# Current_Sensor.net
KiCad netlist of a schematic drawn in Altium Designer
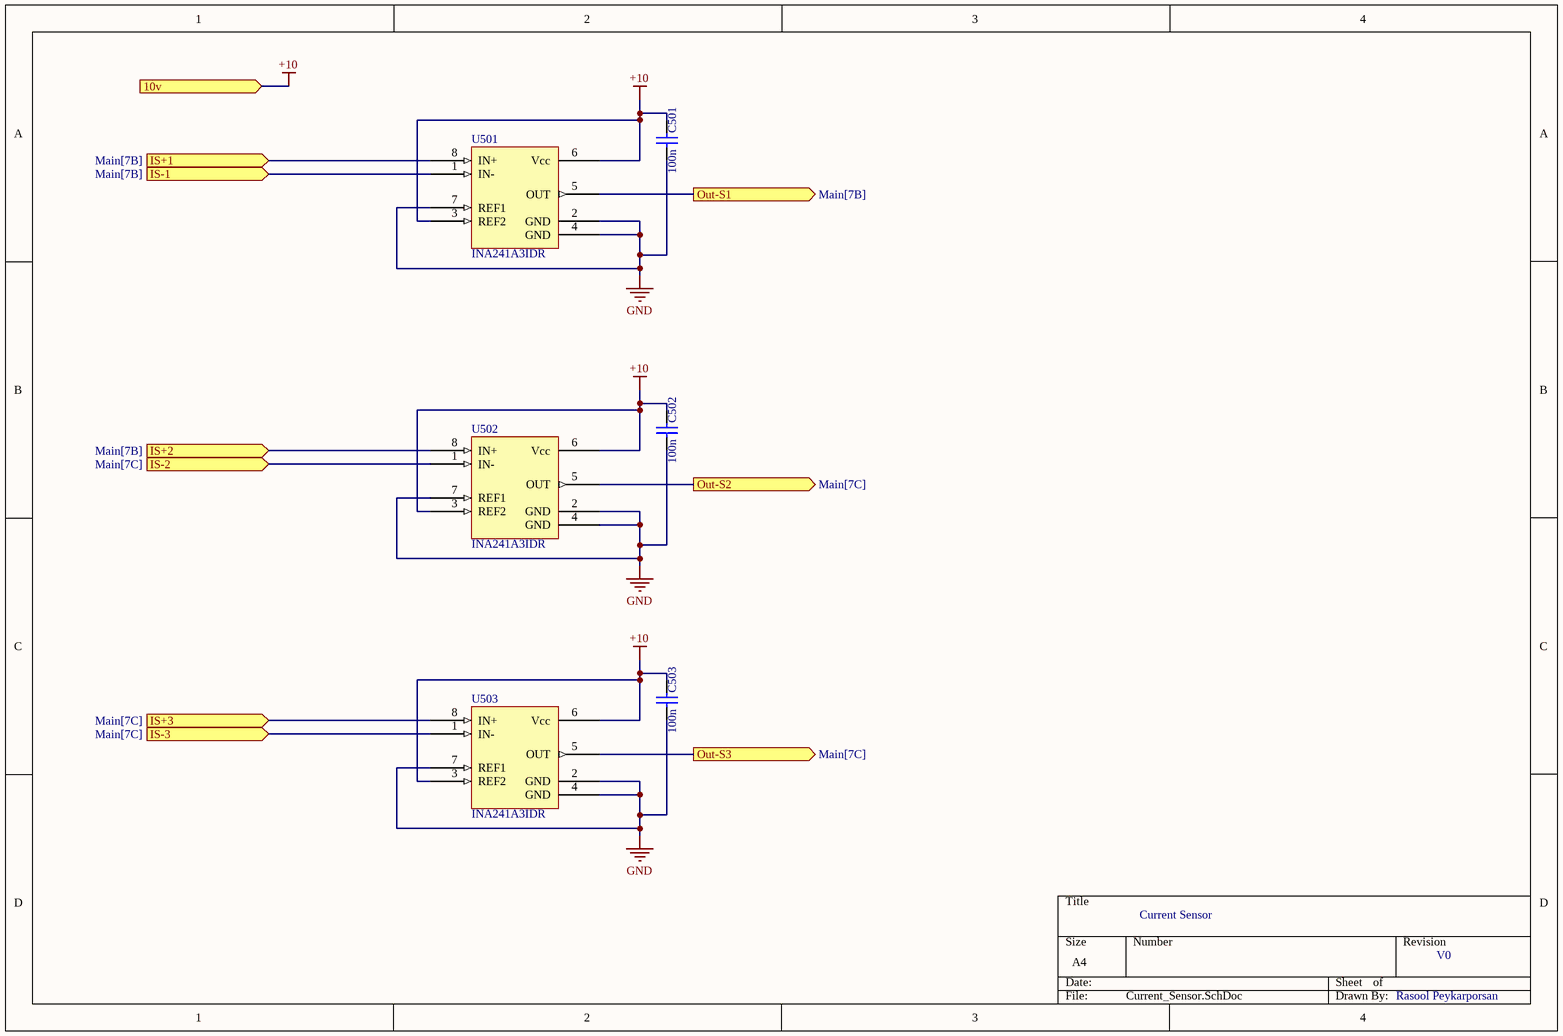
[diagram p0: Current_Sensor.SchDoc]

(export (version "E")
  (design (tool "Eeschema 10.0.6"))
  (components
    (comp (ref "C501")
      (value "100n")
      (footprint "CAP_1206")
      (description "Non Polarized Capacitor, SMD, 1206")
      (libsource (lib "Resistors and Capacitors") (part "CAPN 1206"))
    )
    (comp (ref "C502")
      (value "100n")
      (footprint "CAP_1206")
      (description "Non Polarized Capacitor, SMD, 1206")
      (libsource (lib "Resistors and Capacitors") (part "CAPN 1206"))
    )
    (comp (ref "C503")
      (value "100n")
      (footprint "CAP_1206")
      (description "Non Polarized Capacitor, SMD, 1206")
      (libsource (lib "Resistors and Capacitors") (part "CAPN 1206"))
    )
    (comp (ref "U501")
      (value "INA241A3IDR")
      (footprint "8SOIC-M")
      (description "Current Sense Amplifier 1 Circuit Single-Ended 8-SOIC")
      (libsource (lib "Schematics") (part "INA241A3IDR"))
    )
    (comp (ref "U502")
      (value "INA241A3IDR")
      (footprint "8SOIC-M")
      (description "Current Sense Amplifier 1 Circuit Single-Ended 8-SOIC")
      (libsource (lib "Schematics") (part "INA241A3IDR"))
    )
    (comp (ref "U503")
      (value "INA241A3IDR")
      (footprint "8SOIC-M")
      (description "Current Sense Amplifier 1 Circuit Single-Ended 8-SOIC")
      (libsource (lib "Schematics") (part "INA241A3IDR"))
    )
  )
  (nets
    (net (code "1") (name "+10") (class "Default")
      (node (ref "C501") (pin "2") (pinfunction "2_2") (pintype "passive"))
      (node (ref "C502") (pin "2") (pinfunction "2_2") (pintype "passive"))
      (node (ref "C503") (pin "2") (pinfunction "2_2") (pintype "passive"))
      (node (ref "U501") (pin "3") (pinfunction "REF2_3") (pintype "input"))
      (node (ref "U501") (pin "6") (pinfunction "Vcc_6") (pintype "power_in"))
      (node (ref "U502") (pin "3") (pinfunction "REF2_3") (pintype "input"))
      (node (ref "U502") (pin "6") (pinfunction "Vcc_6") (pintype "power_in"))
      (node (ref "U503") (pin "3") (pinfunction "REF2_3") (pintype "input"))
      (node (ref "U503") (pin "6") (pinfunction "Vcc_6") (pintype "power_in"))
    )
    (net (code "2") (name "/IS+1") (class "Default")
      (node (ref "U501") (pin "8") (pinfunction "IN+_8") (pintype "input"))
    )
    (net (code "3") (name "/IS+2") (class "Default")
      (node (ref "U502") (pin "8") (pinfunction "IN+_8") (pintype "input"))
    )
    (net (code "4") (name "/IS+3") (class "Default")
      (node (ref "U503") (pin "8") (pinfunction "IN+_8") (pintype "input"))
    )
    (net (code "5") (name "/IS-1") (class "Default")
      (node (ref "U501") (pin "1") (pinfunction "IN-_1") (pintype "input"))
    )
    (net (code "6") (name "/IS-2") (class "Default")
      (node (ref "U502") (pin "1") (pinfunction "IN-_1") (pintype "input"))
    )
    (net (code "7") (name "/IS-3") (class "Default")
      (node (ref "U503") (pin "1") (pinfunction "IN-_1") (pintype "input"))
    )
    (net (code "8") (name "/Out-S1") (class "Default")
      (node (ref "U501") (pin "5") (pinfunction "OUT_5") (pintype "output"))
    )
    (net (code "9") (name "/Out-S2") (class "Default")
      (node (ref "U502") (pin "5") (pinfunction "OUT_5") (pintype "output"))
    )
    (net (code "10") (name "/Out-S3") (class "Default")
      (node (ref "U503") (pin "5") (pinfunction "OUT_5") (pintype "output"))
    )
    (net (code "11") (name "GND") (class "Default")
      (node (ref "C501") (pin "1") (pinfunction "1_1") (pintype "passive"))
      (node (ref "C502") (pin "1") (pinfunction "1_1") (pintype "passive"))
      (node (ref "C503") (pin "1") (pinfunction "1_1") (pintype "passive"))
      (node (ref "U501") (pin "2") (pinfunction "GND_2") (pintype "power_in"))
      (node (ref "U501") (pin "4") (pinfunction "GND_4") (pintype "passive"))
      (node (ref "U501") (pin "7") (pinfunction "REF1_7") (pintype "input"))
      (node (ref "U502") (pin "2") (pinfunction "GND_2") (pintype "power_in"))
      (node (ref "U502") (pin "4") (pinfunction "GND_4") (pintype "passive"))
      (node (ref "U502") (pin "7") (pinfunction "REF1_7") (pintype "input"))
      (node (ref "U503") (pin "2") (pinfunction "GND_2") (pintype "power_in"))
      (node (ref "U503") (pin "4") (pinfunction "GND_4") (pintype "passive"))
      (node (ref "U503") (pin "7") (pinfunction "REF1_7") (pintype "input"))
    )
  )
)
